# led_dip.net
KiCad netlist of a schematic drawn in EAGLE
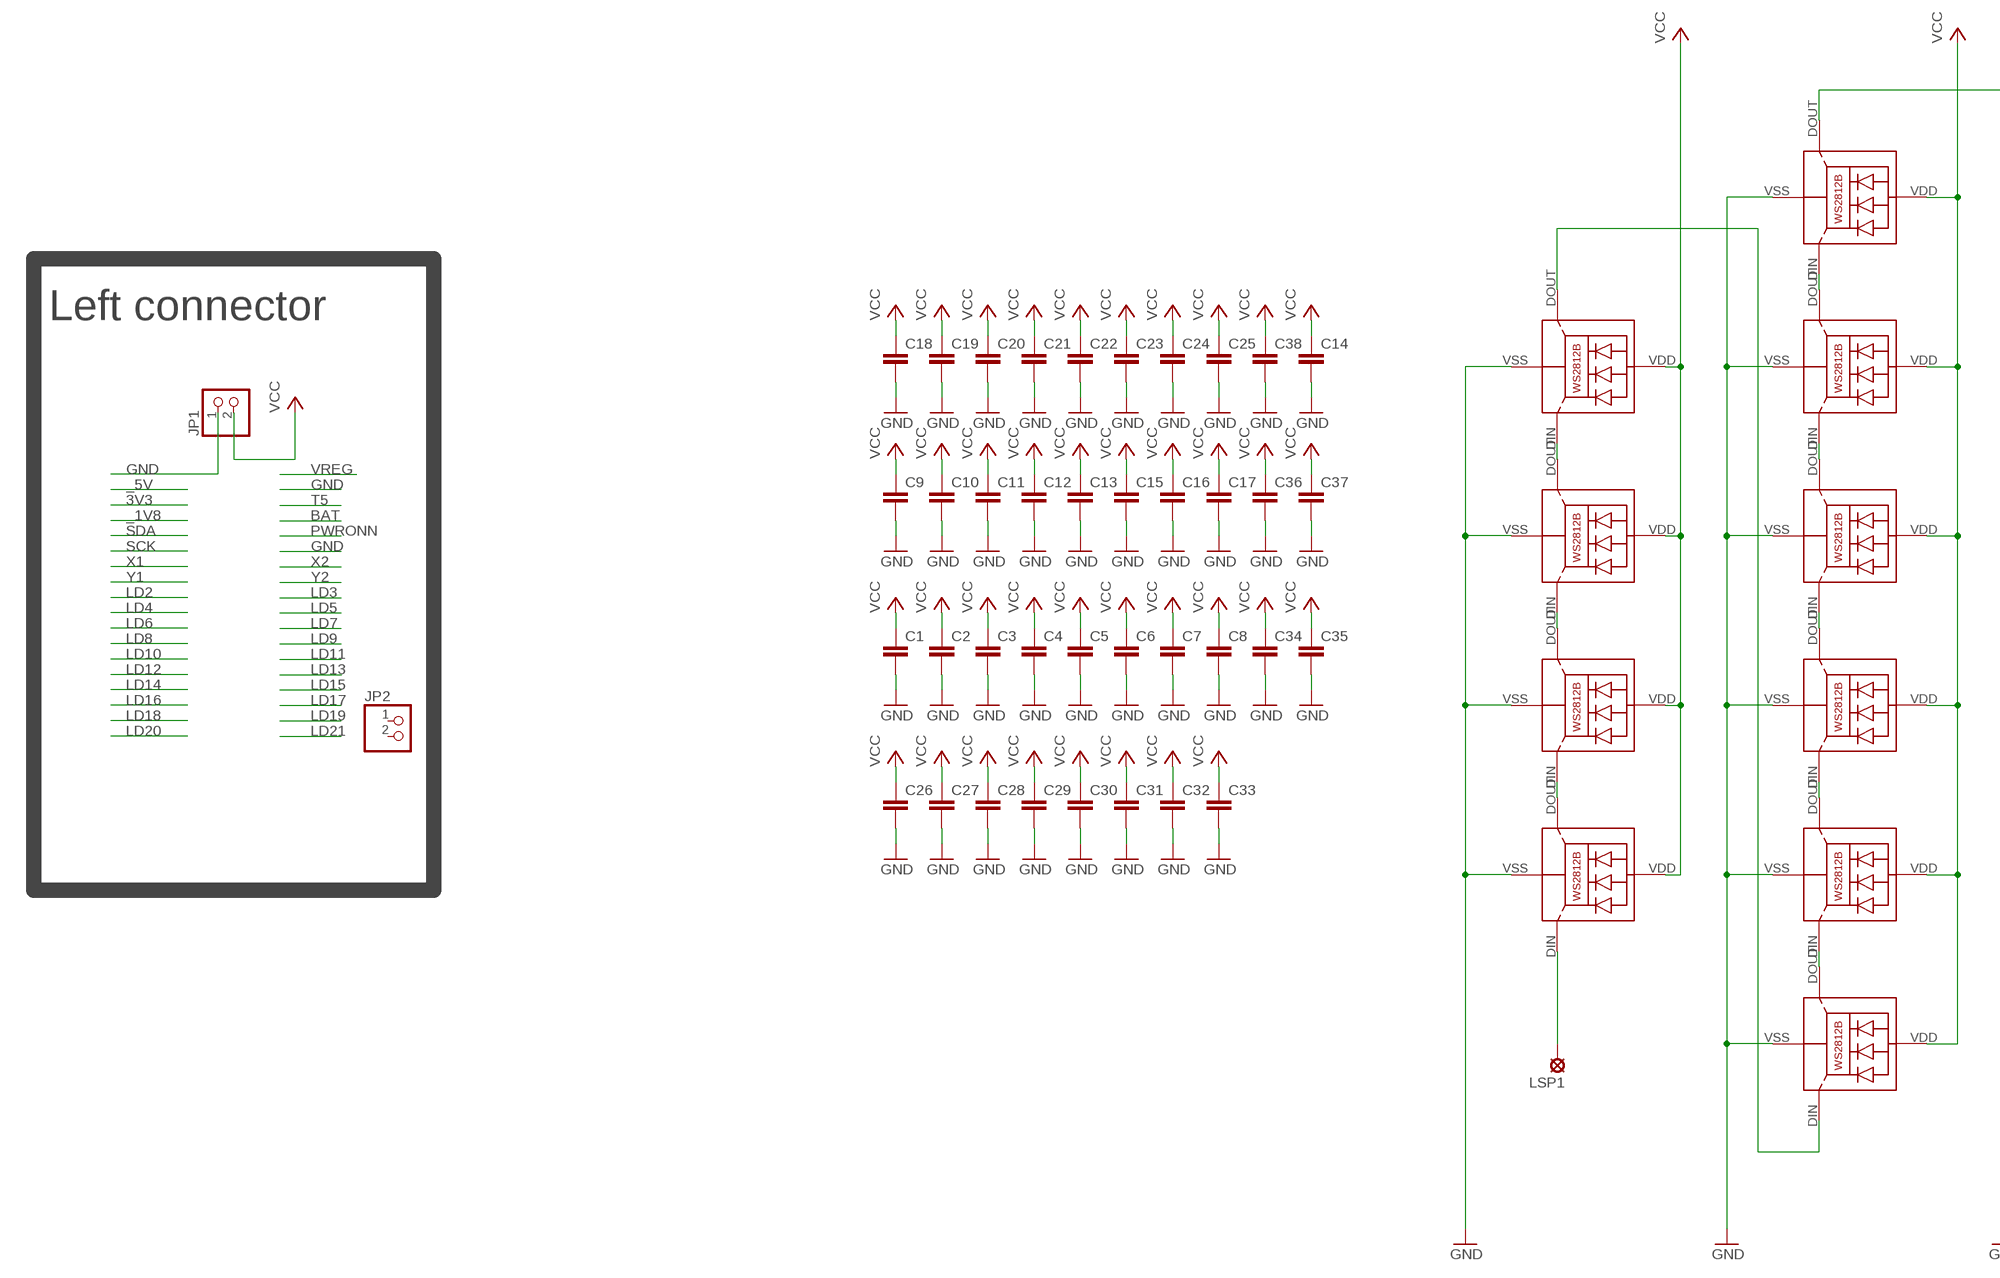
[diagram p0: schematic, sheet 1, part 1 of 2]
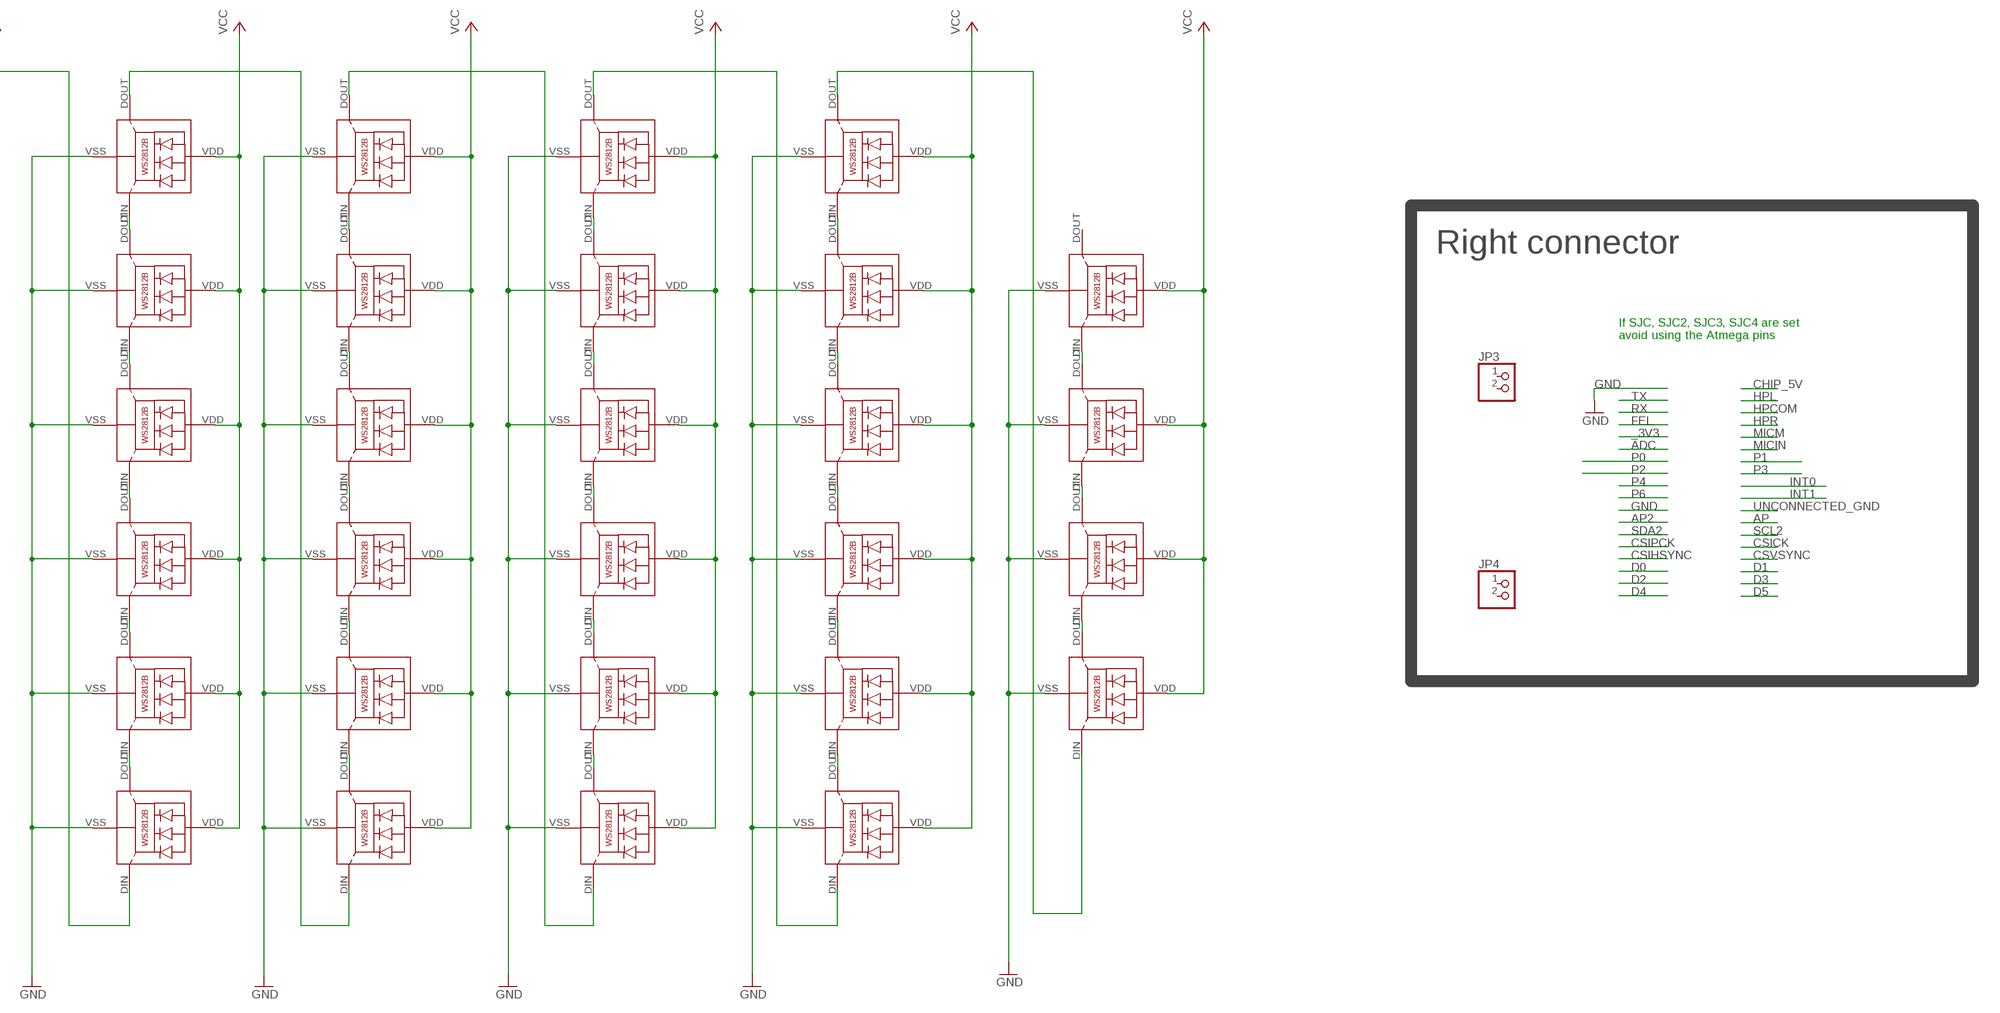
[diagram p1: schematic, sheet 1, part 2 of 2]

(export (version "E")
  (design (tool "Eeschema 10.0.6"))
  (components
    (comp (ref "C1")
      (value "C-EUC0805")
      (footprint "eagle-import:C0805")
      (libsource (lib "eagle-import") (part "C-EUC0805"))
    )
    (comp (ref "C2")
      (value "C-EUC0805")
      (footprint "eagle-import:C0805")
      (libsource (lib "eagle-import") (part "C-EUC0805"))
    )
    (comp (ref "C3")
      (value "C-EUC0805")
      (footprint "eagle-import:C0805")
      (libsource (lib "eagle-import") (part "C-EUC0805"))
    )
    (comp (ref "C4")
      (value "C-EUC0805")
      (footprint "eagle-import:C0805")
      (libsource (lib "eagle-import") (part "C-EUC0805"))
    )
    (comp (ref "C5")
      (value "C-EUC0805")
      (footprint "eagle-import:C0805")
      (libsource (lib "eagle-import") (part "C-EUC0805"))
    )
    (comp (ref "C6")
      (value "C-EUC0805")
      (footprint "eagle-import:C0805")
      (libsource (lib "eagle-import") (part "C-EUC0805"))
    )
    (comp (ref "C7")
      (value "C-EUC0805")
      (footprint "eagle-import:C0805")
      (libsource (lib "eagle-import") (part "C-EUC0805"))
    )
    (comp (ref "C8")
      (value "C-EUC0805")
      (footprint "eagle-import:C0805")
      (libsource (lib "eagle-import") (part "C-EUC0805"))
    )
    (comp (ref "C9")
      (value "C-EUC0805")
      (footprint "eagle-import:C0805")
      (libsource (lib "eagle-import") (part "C-EUC0805"))
    )
    (comp (ref "C10")
      (value "C-EUC0805")
      (footprint "eagle-import:C0805")
      (libsource (lib "eagle-import") (part "C-EUC0805"))
    )
    (comp (ref "C11")
      (value "C-EUC0805")
      (footprint "eagle-import:C0805")
      (libsource (lib "eagle-import") (part "C-EUC0805"))
    )
    (comp (ref "C12")
      (value "C-EUC0805")
      (footprint "eagle-import:C0805")
      (libsource (lib "eagle-import") (part "C-EUC0805"))
    )
    (comp (ref "C13")
      (value "C-EUC0805")
      (footprint "eagle-import:C0805")
      (libsource (lib "eagle-import") (part "C-EUC0805"))
    )
    (comp (ref "C14")
      (value "C-EUC0805")
      (footprint "eagle-import:C0805")
      (libsource (lib "eagle-import") (part "C-EUC0805"))
    )
    (comp (ref "C15")
      (value "C-EUC0805")
      (footprint "eagle-import:C0805")
      (libsource (lib "eagle-import") (part "C-EUC0805"))
    )
    (comp (ref "C16")
      (value "C-EUC0805")
      (footprint "eagle-import:C0805")
      (libsource (lib "eagle-import") (part "C-EUC0805"))
    )
    (comp (ref "C17")
      (value "C-EUC0805")
      (footprint "eagle-import:C0805")
      (libsource (lib "eagle-import") (part "C-EUC0805"))
    )
    (comp (ref "C18")
      (value "C-EUC0805")
      (footprint "eagle-import:C0805")
      (libsource (lib "eagle-import") (part "C-EUC0805"))
    )
    (comp (ref "C19")
      (value "C-EUC0805")
      (footprint "eagle-import:C0805")
      (libsource (lib "eagle-import") (part "C-EUC0805"))
    )
    (comp (ref "C20")
      (value "C-EUC0805")
      (footprint "eagle-import:C0805")
      (libsource (lib "eagle-import") (part "C-EUC0805"))
    )
    (comp (ref "C21")
      (value "C-EUC0805")
      (footprint "eagle-import:C0805")
      (libsource (lib "eagle-import") (part "C-EUC0805"))
    )
    (comp (ref "C22")
      (value "C-EUC0805")
      (footprint "eagle-import:C0805")
      (libsource (lib "eagle-import") (part "C-EUC0805"))
    )
    (comp (ref "C23")
      (value "C-EUC0805")
      (footprint "eagle-import:C0805")
      (libsource (lib "eagle-import") (part "C-EUC0805"))
    )
    (comp (ref "C24")
      (value "C-EUC0805")
      (footprint "eagle-import:C0805")
      (libsource (lib "eagle-import") (part "C-EUC0805"))
    )
    (comp (ref "C25")
      (value "C-EUC0805")
      (footprint "eagle-import:C0805")
      (libsource (lib "eagle-import") (part "C-EUC0805"))
    )
    (comp (ref "C26")
      (value "C-EUC0805")
      (footprint "eagle-import:C0805")
      (libsource (lib "eagle-import") (part "C-EUC0805"))
    )
    (comp (ref "C27")
      (value "C-EUC0805")
      (footprint "eagle-import:C0805")
      (libsource (lib "eagle-import") (part "C-EUC0805"))
    )
    (comp (ref "C28")
      (value "C-EUC0805")
      (footprint "eagle-import:C0805")
      (libsource (lib "eagle-import") (part "C-EUC0805"))
    )
    (comp (ref "C29")
      (value "C-EUC0805")
      (footprint "eagle-import:C0805")
      (libsource (lib "eagle-import") (part "C-EUC0805"))
    )
    (comp (ref "C30")
      (value "C-EUC0805")
      (footprint "eagle-import:C0805")
      (libsource (lib "eagle-import") (part "C-EUC0805"))
    )
    (comp (ref "C31")
      (value "C-EUC0805")
      (footprint "eagle-import:C0805")
      (libsource (lib "eagle-import") (part "C-EUC0805"))
    )
    (comp (ref "C32")
      (value "C-EUC0805")
      (footprint "eagle-import:C0805")
      (libsource (lib "eagle-import") (part "C-EUC0805"))
    )
    (comp (ref "C33")
      (value "C-EUC0805")
      (footprint "eagle-import:C0805")
      (libsource (lib "eagle-import") (part "C-EUC0805"))
    )
    (comp (ref "C34")
      (value "C-EUC0805")
      (footprint "eagle-import:C0805")
      (libsource (lib "eagle-import") (part "C-EUC0805"))
    )
    (comp (ref "C35")
      (value "C-EUC0805")
      (footprint "eagle-import:C0805")
      (libsource (lib "eagle-import") (part "C-EUC0805"))
    )
    (comp (ref "C36")
      (value "C-EUC0805")
      (footprint "eagle-import:C0805")
      (libsource (lib "eagle-import") (part "C-EUC0805"))
    )
    (comp (ref "C37")
      (value "C-EUC0805")
      (footprint "eagle-import:C0805")
      (libsource (lib "eagle-import") (part "C-EUC0805"))
    )
    (comp (ref "C38")
      (value "C-EUC0805")
      (footprint "eagle-import:C0805")
      (libsource (lib "eagle-import") (part "C-EUC0805"))
    )
    (comp (ref "JP1")
      (value "PINHD-1X2")
      (footprint "eagle-import:1X02")
      (libsource (lib "eagle-import") (part "PINHD-1X2"))
    )
    (comp (ref "JP2")
      (value "PINHD-1X2")
      (footprint "eagle-import:1X02")
      (libsource (lib "eagle-import") (part "PINHD-1X2"))
    )
    (comp (ref "JP3")
      (value "PINHD-1X2")
      (footprint "eagle-import:1X02")
      (libsource (lib "eagle-import") (part "PINHD-1X2"))
    )
    (comp (ref "JP4")
      (value "PINHD-1X2")
      (footprint "eagle-import:1X02")
      (libsource (lib "eagle-import") (part "PINHD-1X2"))
    )
    (comp (ref "LED1")
      (value "WS2812B")
      (footprint "eagle-import:WS2812B")
      (libsource (lib "eagle-import") (part "WS2812B"))
    )
    (comp (ref "LED2")
      (value "WS2812B")
      (footprint "eagle-import:WS2812B")
      (libsource (lib "eagle-import") (part "WS2812B"))
    )
    (comp (ref "LED3")
      (value "WS2812B")
      (footprint "eagle-import:WS2812B")
      (libsource (lib "eagle-import") (part "WS2812B"))
    )
    (comp (ref "LED4")
      (value "WS2812B")
      (footprint "eagle-import:WS2812B")
      (libsource (lib "eagle-import") (part "WS2812B"))
    )
    (comp (ref "LED5")
      (value "WS2812B")
      (footprint "eagle-import:WS2812B")
      (libsource (lib "eagle-import") (part "WS2812B"))
    )
    (comp (ref "LED6")
      (value "WS2812B")
      (footprint "eagle-import:WS2812B")
      (libsource (lib "eagle-import") (part "WS2812B"))
    )
    (comp (ref "LED7")
      (value "WS2812B")
      (footprint "eagle-import:WS2812B")
      (libsource (lib "eagle-import") (part "WS2812B"))
    )
    (comp (ref "LED8")
      (value "WS2812B")
      (footprint "eagle-import:WS2812B")
      (libsource (lib "eagle-import") (part "WS2812B"))
    )
    (comp (ref "LED9")
      (value "WS2812B")
      (footprint "eagle-import:WS2812B")
      (libsource (lib "eagle-import") (part "WS2812B"))
    )
    (comp (ref "LED10")
      (value "WS2812B")
      (footprint "eagle-import:WS2812B")
      (libsource (lib "eagle-import") (part "WS2812B"))
    )
    (comp (ref "LED11")
      (value "WS2812B")
      (footprint "eagle-import:WS2812B")
      (libsource (lib "eagle-import") (part "WS2812B"))
    )
    (comp (ref "LED12")
      (value "WS2812B")
      (footprint "eagle-import:WS2812B")
      (libsource (lib "eagle-import") (part "WS2812B"))
    )
    (comp (ref "LED13")
      (value "WS2812B")
      (footprint "eagle-import:WS2812B")
      (libsource (lib "eagle-import") (part "WS2812B"))
    )
    (comp (ref "LED14")
      (value "WS2812B")
      (footprint "eagle-import:WS2812B")
      (libsource (lib "eagle-import") (part "WS2812B"))
    )
    (comp (ref "LED15")
      (value "WS2812B")
      (footprint "eagle-import:WS2812B")
      (libsource (lib "eagle-import") (part "WS2812B"))
    )
    (comp (ref "LED16")
      (value "WS2812B")
      (footprint "eagle-import:WS2812B")
      (libsource (lib "eagle-import") (part "WS2812B"))
    )
    (comp (ref "LED17")
      (value "WS2812B")
      (footprint "eagle-import:WS2812B")
      (libsource (lib "eagle-import") (part "WS2812B"))
    )
    (comp (ref "LED18")
      (value "WS2812B")
      (footprint "eagle-import:WS2812B")
      (libsource (lib "eagle-import") (part "WS2812B"))
    )
    (comp (ref "LED19")
      (value "WS2812B")
      (footprint "eagle-import:WS2812B")
      (libsource (lib "eagle-import") (part "WS2812B"))
    )
    (comp (ref "LED20")
      (value "WS2812B")
      (footprint "eagle-import:WS2812B")
      (libsource (lib "eagle-import") (part "WS2812B"))
    )
    (comp (ref "LED21")
      (value "WS2812B")
      (footprint "eagle-import:WS2812B")
      (libsource (lib "eagle-import") (part "WS2812B"))
    )
    (comp (ref "LED22")
      (value "WS2812B")
      (footprint "eagle-import:WS2812B")
      (libsource (lib "eagle-import") (part "WS2812B"))
    )
    (comp (ref "LED23")
      (value "WS2812B")
      (footprint "eagle-import:WS2812B")
      (libsource (lib "eagle-import") (part "WS2812B"))
    )
    (comp (ref "LED24")
      (value "WS2812B")
      (footprint "eagle-import:WS2812B")
      (libsource (lib "eagle-import") (part "WS2812B"))
    )
    (comp (ref "LED25")
      (value "WS2812B")
      (footprint "eagle-import:WS2812B")
      (libsource (lib "eagle-import") (part "WS2812B"))
    )
    (comp (ref "LED26")
      (value "WS2812B")
      (footprint "eagle-import:WS2812B")
      (libsource (lib "eagle-import") (part "WS2812B"))
    )
    (comp (ref "LED27")
      (value "WS2812B")
      (footprint "eagle-import:WS2812B")
      (libsource (lib "eagle-import") (part "WS2812B"))
    )
    (comp (ref "LED28")
      (value "WS2812B")
      (footprint "eagle-import:WS2812B")
      (libsource (lib "eagle-import") (part "WS2812B"))
    )
    (comp (ref "LED30")
      (value "WS2812B")
      (footprint "eagle-import:WS2812B")
      (libsource (lib "eagle-import") (part "WS2812B"))
    )
    (comp (ref "LED31")
      (value "WS2812B")
      (footprint "eagle-import:WS2812B")
      (libsource (lib "eagle-import") (part "WS2812B"))
    )
    (comp (ref "LED32")
      (value "WS2812B")
      (footprint "eagle-import:WS2812B")
      (libsource (lib "eagle-import") (part "WS2812B"))
    )
    (comp (ref "LED33")
      (value "WS2812B")
      (footprint "eagle-import:WS2812B")
      (libsource (lib "eagle-import") (part "WS2812B"))
    )
    (comp (ref "LED34")
      (value "WS2812B")
      (footprint "eagle-import:WS2812B")
      (libsource (lib "eagle-import") (part "WS2812B"))
    )
    (comp (ref "LED35")
      (value "WS2812B")
      (footprint "eagle-import:WS2812B")
      (libsource (lib "eagle-import") (part "WS2812B"))
    )
    (comp (ref "LED36")
      (value "WS2812B")
      (footprint "eagle-import:WS2812B")
      (libsource (lib "eagle-import") (part "WS2812B"))
    )
    (comp (ref "LED37")
      (value "WS2812B")
      (footprint "eagle-import:WS2812B")
      (libsource (lib "eagle-import") (part "WS2812B"))
    )
    (comp (ref "LED38")
      (value "WS2812B")
      (footprint "eagle-import:WS2812B")
      (libsource (lib "eagle-import") (part "WS2812B"))
    )
    (comp (ref "LED39")
      (value "WS2812B")
      (footprint "eagle-import:WS2812B")
      (libsource (lib "eagle-import") (part "WS2812B"))
    )
    (comp (ref "LSP1")
      (value "LSP10")
      (footprint "eagle-import:LSP10")
      (libsource (lib "eagle-import") (part "LSP10"))
    )
  )
  (nets
    (net (code "68") (name "GND") (class "Default")
      (node (ref "C1") (pin "2") (pinfunction "2_2") (pintype "passive"))
      (node (ref "C10") (pin "2") (pinfunction "2_2") (pintype "passive"))
      (node (ref "C11") (pin "2") (pinfunction "2_2") (pintype "passive"))
      (node (ref "C12") (pin "2") (pinfunction "2_2") (pintype "passive"))
      (node (ref "C13") (pin "2") (pinfunction "2_2") (pintype "passive"))
      (node (ref "C14") (pin "2") (pinfunction "2_2") (pintype "passive"))
      (node (ref "C15") (pin "2") (pinfunction "2_2") (pintype "passive"))
      (node (ref "C16") (pin "2") (pinfunction "2_2") (pintype "passive"))
      (node (ref "C17") (pin "2") (pinfunction "2_2") (pintype "passive"))
      (node (ref "C18") (pin "2") (pinfunction "2_2") (pintype "passive"))
      (node (ref "C19") (pin "2") (pinfunction "2_2") (pintype "passive"))
      (node (ref "C2") (pin "2") (pinfunction "2_2") (pintype "passive"))
      (node (ref "C20") (pin "2") (pinfunction "2_2") (pintype "passive"))
      (node (ref "C21") (pin "2") (pinfunction "2_2") (pintype "passive"))
      (node (ref "C22") (pin "2") (pinfunction "2_2") (pintype "passive"))
      (node (ref "C23") (pin "2") (pinfunction "2_2") (pintype "passive"))
      (node (ref "C24") (pin "2") (pinfunction "2_2") (pintype "passive"))
      (node (ref "C25") (pin "2") (pinfunction "2_2") (pintype "passive"))
      (node (ref "C26") (pin "2") (pinfunction "2_2") (pintype "passive"))
      (node (ref "C27") (pin "2") (pinfunction "2_2") (pintype "passive"))
      (node (ref "C28") (pin "2") (pinfunction "2_2") (pintype "passive"))
      (node (ref "C29") (pin "2") (pinfunction "2_2") (pintype "passive"))
      (node (ref "C3") (pin "2") (pinfunction "2_2") (pintype "passive"))
      (node (ref "C30") (pin "2") (pinfunction "2_2") (pintype "passive"))
      (node (ref "C31") (pin "2") (pinfunction "2_2") (pintype "passive"))
      (node (ref "C32") (pin "2") (pinfunction "2_2") (pintype "passive"))
      (node (ref "C33") (pin "2") (pinfunction "2_2") (pintype "passive"))
      (node (ref "C34") (pin "2") (pinfunction "2_2") (pintype "passive"))
      (node (ref "C35") (pin "2") (pinfunction "2_2") (pintype "passive"))
      (node (ref "C36") (pin "2") (pinfunction "2_2") (pintype "passive"))
      (node (ref "C37") (pin "2") (pinfunction "2_2") (pintype "passive"))
      (node (ref "C38") (pin "2") (pinfunction "2_2") (pintype "passive"))
      (node (ref "C4") (pin "2") (pinfunction "2_2") (pintype "passive"))
      (node (ref "C5") (pin "2") (pinfunction "2_2") (pintype "passive"))
      (node (ref "C6") (pin "2") (pinfunction "2_2") (pintype "passive"))
      (node (ref "C7") (pin "2") (pinfunction "2_2") (pintype "passive"))
      (node (ref "C8") (pin "2") (pinfunction "2_2") (pintype "passive"))
      (node (ref "C9") (pin "2") (pinfunction "2_2") (pintype "passive"))
      (node (ref "JP1") (pin "1") (pinfunction "1_1") (pintype "passive"))
      (node (ref "LED1") (pin "VSS") (pinfunction "GND_VSS") (pintype "power_in"))
      (node (ref "LED10") (pin "VSS") (pinfunction "GND_VSS") (pintype "power_in"))
      (node (ref "LED11") (pin "VSS") (pinfunction "GND_VSS") (pintype "power_in"))
      (node (ref "LED12") (pin "VSS") (pinfunction "GND_VSS") (pintype "power_in"))
      (node (ref "LED13") (pin "VSS") (pinfunction "GND_VSS") (pintype "power_in"))
      (node (ref "LED14") (pin "VSS") (pinfunction "GND_VSS") (pintype "power_in"))
      (node (ref "LED15") (pin "VSS") (pinfunction "GND_VSS") (pintype "power_in"))
      (node (ref "LED16") (pin "VSS") (pinfunction "GND_VSS") (pintype "power_in"))
      (node (ref "LED17") (pin "VSS") (pinfunction "GND_VSS") (pintype "power_in"))
      (node (ref "LED18") (pin "VSS") (pinfunction "GND_VSS") (pintype "power_in"))
      (node (ref "LED19") (pin "VSS") (pinfunction "GND_VSS") (pintype "power_in"))
      (node (ref "LED2") (pin "VSS") (pinfunction "GND_VSS") (pintype "power_in"))
      (node (ref "LED20") (pin "VSS") (pinfunction "GND_VSS") (pintype "power_in"))
      (node (ref "LED21") (pin "VSS") (pinfunction "GND_VSS") (pintype "power_in"))
      (node (ref "LED22") (pin "VSS") (pinfunction "GND_VSS") (pintype "power_in"))
      (node (ref "LED23") (pin "VSS") (pinfunction "GND_VSS") (pintype "power_in"))
      (node (ref "LED24") (pin "VSS") (pinfunction "GND_VSS") (pintype "power_in"))
      (node (ref "LED25") (pin "VSS") (pinfunction "GND_VSS") (pintype "power_in"))
      (node (ref "LED26") (pin "VSS") (pinfunction "GND_VSS") (pintype "power_in"))
      (node (ref "LED27") (pin "VSS") (pinfunction "GND_VSS") (pintype "power_in"))
      (node (ref "LED28") (pin "VSS") (pinfunction "GND_VSS") (pintype "power_in"))
      (node (ref "LED3") (pin "VSS") (pinfunction "GND_VSS") (pintype "power_in"))
      (node (ref "LED30") (pin "VSS") (pinfunction "GND_VSS") (pintype "power_in"))
      (node (ref "LED31") (pin "VSS") (pinfunction "GND_VSS") (pintype "power_in"))
      (node (ref "LED32") (pin "VSS") (pinfunction "GND_VSS") (pintype "power_in"))
      (node (ref "LED33") (pin "VSS") (pinfunction "GND_VSS") (pintype "power_in"))
      (node (ref "LED34") (pin "VSS") (pinfunction "GND_VSS") (pintype "power_in"))
      (node (ref "LED35") (pin "VSS") (pinfunction "GND_VSS") (pintype "power_in"))
      (node (ref "LED36") (pin "VSS") (pinfunction "GND_VSS") (pintype "power_in"))
      (node (ref "LED37") (pin "VSS") (pinfunction "GND_VSS") (pintype "power_in"))
      (node (ref "LED38") (pin "VSS") (pinfunction "GND_VSS") (pintype "power_in"))
      (node (ref "LED39") (pin "VSS") (pinfunction "GND_VSS") (pintype "power_in"))
      (node (ref "LED4") (pin "VSS") (pinfunction "GND_VSS") (pintype "power_in"))
      (node (ref "LED5") (pin "VSS") (pinfunction "GND_VSS") (pintype "power_in"))
      (node (ref "LED6") (pin "VSS") (pinfunction "GND_VSS") (pintype "power_in"))
      (node (ref "LED7") (pin "VSS") (pinfunction "GND_VSS") (pintype "power_in"))
      (node (ref "LED8") (pin "VSS") (pinfunction "GND_VSS") (pintype "power_in"))
      (node (ref "LED9") (pin "VSS") (pinfunction "GND_VSS") (pintype "power_in"))
    )
    (net (code "69") (name "Net-(LED1-DI)") (class "Default")
      (node (ref "LED1") (pin "DIN") (pinfunction "DI_DIN") (pintype "input"))
      (node (ref "LED3") (pin "DOUT") (pinfunction "DO_DOUT") (pintype "output"))
    )
    (net (code "70") (name "Net-(LED1-DO)") (class "Default")
      (node (ref "LED1") (pin "DOUT") (pinfunction "DO_DOUT") (pintype "output"))
      (node (ref "LED2") (pin "DIN") (pinfunction "DI_DIN") (pintype "input"))
    )
    (net (code "71") (name "Net-(LED2-DO)") (class "Default")
      (node (ref "LED2") (pin "DOUT") (pinfunction "DO_DOUT") (pintype "output"))
      (node (ref "LED28") (pin "DIN") (pinfunction "DI_DIN") (pintype "input"))
    )
    (net (code "72") (name "Net-(LED6-DI)") (class "Default")
      (node (ref "LED6") (pin "DIN") (pinfunction "DI_DIN") (pintype "input"))
      (node (ref "LED9") (pin "DOUT") (pinfunction "DO_DOUT") (pintype "output"))
    )
    (net (code "73") (name "Net-(LED6-DO)") (class "Default")
      (node (ref "LED6") (pin "DOUT") (pinfunction "DO_DOUT") (pintype "output"))
      (node (ref "LED7") (pin "DIN") (pinfunction "DI_DIN") (pintype "input"))
    )
    (net (code "74") (name "Net-(LED7-DO)") (class "Default")
      (node (ref "LED7") (pin "DOUT") (pinfunction "DO_DOUT") (pintype "output"))
      (node (ref "LED8") (pin "DIN") (pinfunction "DI_DIN") (pintype "input"))
    )
    (net (code "75") (name "Net-(LED10-DI)") (class "Default")
      (node (ref "LED10") (pin "DIN") (pinfunction "DI_DIN") (pintype "input"))
      (node (ref "LED25") (pin "DOUT") (pinfunction "DO_DOUT") (pintype "output"))
    )
    (net (code "76") (name "Net-(LED10-DO)") (class "Default")
      (node (ref "LED10") (pin "DOUT") (pinfunction "DO_DOUT") (pintype "output"))
      (node (ref "LED19") (pin "DIN") (pinfunction "DI_DIN") (pintype "input"))
    )
    (net (code "77") (name "Net-(LED11-DI)") (class "Default")
      (node (ref "LED11") (pin "DIN") (pinfunction "DI_DIN") (pintype "input"))
      (node (ref "LED13") (pin "DOUT") (pinfunction "DO_DOUT") (pintype "output"))
    )
    (net (code "78") (name "Net-(LED11-DO)") (class "Default")
      (node (ref "LED11") (pin "DOUT") (pinfunction "DO_DOUT") (pintype "output"))
      (node (ref "LED25") (pin "DIN") (pinfunction "DI_DIN") (pintype "input"))
    )
    (net (code "79") (name "Net-(LED12-DI)") (class "Default")
      (node (ref "LED12") (pin "DIN") (pinfunction "DI_DIN") (pintype "input"))
      (node (ref "LED20") (pin "DOUT") (pinfunction "DO_DOUT") (pintype "output"))
    )
    (net (code "80") (name "Net-(LED12-DO)") (class "Default")
      (node (ref "LED12") (pin "DOUT") (pinfunction "DO_DOUT") (pintype "output"))
      (node (ref "LED9") (pin "DIN") (pinfunction "DI_DIN") (pintype "input"))
    )
    (net (code "81") (name "Net-(LED13-DI)") (class "Default")
      (node (ref "LED13") (pin "DIN") (pinfunction "DI_DIN") (pintype "input"))
      (node (ref "LED15") (pin "DOUT") (pinfunction "DO_DOUT") (pintype "output"))
    )
    (net (code "82") (name "Net-(LED14-DI)") (class "Default")
      (node (ref "LED14") (pin "DIN") (pinfunction "DI_DIN") (pintype "input"))
      (node (ref "LSP1") (pin "MP") (pinfunction "MP_MP") (pintype "passive"))
    )
    (net (code "83") (name "Net-(LED14-DO)") (class "Default")
      (node (ref "LED14") (pin "DOUT") (pinfunction "DO_DOUT") (pintype "output"))
      (node (ref "LED16") (pin "DIN") (pinfunction "DI_DIN") (pintype "input"))
    )
    (net (code "84") (name "Net-(LED15-DI)") (class "Default")
      (node (ref "LED15") (pin "DIN") (pinfunction "DI_DIN") (pintype "input"))
      (node (ref "LED33") (pin "DOUT") (pinfunction "DO_DOUT") (pintype "output"))
    )
    (net (code "85") (name "Net-(LED16-DO)") (class "Default")
      (node (ref "LED16") (pin "DOUT") (pinfunction "DO_DOUT") (pintype "output"))
      (node (ref "LED20") (pin "DIN") (pinfunction "DI_DIN") (pintype "input"))
    )
    (net (code "86") (name "Net-(LED17-DI)") (class "Default")
      (node (ref "LED17") (pin "DIN") (pinfunction "DI_DIN") (pintype "input"))
      (node (ref "LED22") (pin "DOUT") (pinfunction "DO_DOUT") (pintype "output"))
    )
    (net (code "87") (name "Net-(LED17-DO)") (class "Default")
      (node (ref "LED17") (pin "DOUT") (pinfunction "DO_DOUT") (pintype "output"))
      (node (ref "LED27") (pin "DIN") (pinfunction "DI_DIN") (pintype "input"))
    )
    (net (code "88") (name "Net-(LED18-DI)") (class "Default")
      (node (ref "LED18") (pin "DIN") (pinfunction "DI_DIN") (pintype "input"))
      (node (ref "LED8") (pin "DOUT") (pinfunction "DO_DOUT") (pintype "output"))
    )
    (net (code "89") (name "Net-(LED18-DO)") (class "Default")
      (node (ref "LED18") (pin "DOUT") (pinfunction "DO_DOUT") (pintype "output"))
      (node (ref "LED3") (pin "DIN") (pinfunction "DI_DIN") (pintype "input"))
    )
    (net (code "90") (name "Net-(LED19-DO)") (class "Default")
      (node (ref "LED19") (pin "DOUT") (pinfunction "DO_DOUT") (pintype "output"))
      (node (ref "LED26") (pin "DIN") (pinfunction "DI_DIN") (pintype "input"))
    )
    (net (code "91") (name "Net-(LED21-DI)") (class "Default")
      (node (ref "LED21") (pin "DIN") (pinfunction "DI_DIN") (pintype "input"))
      (node (ref "LED26") (pin "DOUT") (pinfunction "DO_DOUT") (pintype "output"))
    )
    (net (code "92") (name "Net-(LED21-DO)") (class "Default")
      (node (ref "LED21") (pin "DOUT") (pinfunction "DO_DOUT") (pintype "output"))
      (node (ref "LED23") (pin "DIN") (pinfunction "DI_DIN") (pintype "input"))
    )
    (net (code "93") (name "Net-(LED22-DI)") (class "Default")
      (node (ref "LED22") (pin "DIN") (pinfunction "DI_DIN") (pintype "input"))
      (node (ref "LED28") (pin "DOUT") (pinfunction "DO_DOUT") (pintype "output"))
    )
    (net (code "94") (name "Net-(LED23-DO)") (class "Default")
      (node (ref "LED23") (pin "DOUT") (pinfunction "DO_DOUT") (pintype "output"))
      (node (ref "LED24") (pin "DIN") (pinfunction "DI_DIN") (pintype "input"))
    )
    (net (code "95") (name "Net-(LED27-DO)") (class "Default")
      (node (ref "LED27") (pin "DOUT") (pinfunction "DO_DOUT") (pintype "output"))
      (node (ref "LED37") (pin "DIN") (pinfunction "DI_DIN") (pintype "input"))
    )
    (net (code "96") (name "Net-(LED30-DI)") (class "Default")
      (node (ref "LED30") (pin "DIN") (pinfunction "DI_DIN") (pintype "input"))
      (node (ref "LED31") (pin "DOUT") (pinfunction "DO_DOUT") (pintype "output"))
    )
    (net (code "97") (name "Net-(LED30-DO)") (class "Default")
      (node (ref "LED30") (pin "DOUT") (pinfunction "DO_DOUT") (pintype "output"))
      (node (ref "LED38") (pin "DIN") (pinfunction "DI_DIN") (pintype "input"))
    )
    (net (code "98") (name "Net-(LED31-DI)") (class "Default")
      (node (ref "LED31") (pin "DIN") (pinfunction "DI_DIN") (pintype "input"))
      (node (ref "LED4") (pin "DOUT") (pinfunction "DO_DOUT") (pintype "output"))
    )
    (net (code "99") (name "Net-(LED32-DI)") (class "Default")
      (node (ref "LED32") (pin "DIN") (pinfunction "DI_DIN") (pintype "input"))
      (node (ref "LED5") (pin "DOUT") (pinfunction "DO_DOUT") (pintype "output"))
    )
    (net (code "100") (name "Net-(LED32-DO)") (class "Default")
      (node (ref "LED32") (pin "DOUT") (pinfunction "DO_DOUT") (pintype "output"))
      (node (ref "LED33") (pin "DIN") (pinfunction "DI_DIN") (pintype "input"))
    )
    (net (code "101") (name "Net-(LED34-DI)") (class "Default")
      (node (ref "LED34") (pin "DIN") (pinfunction "DI_DIN") (pintype "input"))
      (node (ref "LED36") (pin "DOUT") (pinfunction "DO_DOUT") (pintype "output"))
    )
    (net (code "102") (name "Net-(LED34-DO)") (class "Default")
      (node (ref "LED34") (pin "DOUT") (pinfunction "DO_DOUT") (pintype "output"))
      (node (ref "LED4") (pin "DIN") (pinfunction "DI_DIN") (pintype "input"))
    )
    (net (code "103") (name "Net-(LED35-DI)") (class "Default")
      (node (ref "LED35") (pin "DIN") (pinfunction "DI_DIN") (pintype "input"))
      (node (ref "LED39") (pin "DOUT") (pinfunction "DO_DOUT") (pintype "output"))
    )
    (net (code "104") (name "Net-(LED35-DO)") (class "Default")
      (node (ref "LED35") (pin "DOUT") (pinfunction "DO_DOUT") (pintype "output"))
      (node (ref "LED5") (pin "DIN") (pinfunction "DI_DIN") (pintype "input"))
    )
    (net (code "105") (name "Net-(LED36-DI)") (class "Default")
      (node (ref "LED36") (pin "DIN") (pinfunction "DI_DIN") (pintype "input"))
      (node (ref "LED37") (pin "DOUT") (pinfunction "DO_DOUT") (pintype "output"))
    )
    (net (code "106") (name "Net-(LED38-DO)") (class "Default")
      (node (ref "LED38") (pin "DOUT") (pinfunction "DO_DOUT") (pintype "output"))
      (node (ref "LED39") (pin "DIN") (pinfunction "DI_DIN") (pintype "input"))
    )
    (net (code "107") (name "VCC") (class "Default")
      (node (ref "C1") (pin "1") (pinfunction "1_1") (pintype "passive"))
      (node (ref "C10") (pin "1") (pinfunction "1_1") (pintype "passive"))
      (node (ref "C11") (pin "1") (pinfunction "1_1") (pintype "passive"))
      (node (ref "C12") (pin "1") (pinfunction "1_1") (pintype "passive"))
      (node (ref "C13") (pin "1") (pinfunction "1_1") (pintype "passive"))
      (node (ref "C14") (pin "1") (pinfunction "1_1") (pintype "passive"))
      (node (ref "C15") (pin "1") (pinfunction "1_1") (pintype "passive"))
      (node (ref "C16") (pin "1") (pinfunction "1_1") (pintype "passive"))
      (node (ref "C17") (pin "1") (pinfunction "1_1") (pintype "passive"))
      (node (ref "C18") (pin "1") (pinfunction "1_1") (pintype "passive"))
      (node (ref "C19") (pin "1") (pinfunction "1_1") (pintype "passive"))
      (node (ref "C2") (pin "1") (pinfunction "1_1") (pintype "passive"))
      (node (ref "C20") (pin "1") (pinfunction "1_1") (pintype "passive"))
      (node (ref "C21") (pin "1") (pinfunction "1_1") (pintype "passive"))
      (node (ref "C22") (pin "1") (pinfunction "1_1") (pintype "passive"))
      (node (ref "C23") (pin "1") (pinfunction "1_1") (pintype "passive"))
      (node (ref "C24") (pin "1") (pinfunction "1_1") (pintype "passive"))
      (node (ref "C25") (pin "1") (pinfunction "1_1") (pintype "passive"))
      (node (ref "C26") (pin "1") (pinfunction "1_1") (pintype "passive"))
      (node (ref "C27") (pin "1") (pinfunction "1_1") (pintype "passive"))
      (node (ref "C28") (pin "1") (pinfunction "1_1") (pintype "passive"))
      (node (ref "C29") (pin "1") (pinfunction "1_1") (pintype "passive"))
      (node (ref "C3") (pin "1") (pinfunction "1_1") (pintype "passive"))
      (node (ref "C30") (pin "1") (pinfunction "1_1") (pintype "passive"))
      (node (ref "C31") (pin "1") (pinfunction "1_1") (pintype "passive"))
      (node (ref "C32") (pin "1") (pinfunction "1_1") (pintype "passive"))
      (node (ref "C33") (pin "1") (pinfunction "1_1") (pintype "passive"))
      (node (ref "C34") (pin "1") (pinfunction "1_1") (pintype "passive"))
      (node (ref "C35") (pin "1") (pinfunction "1_1") (pintype "passive"))
      (node (ref "C36") (pin "1") (pinfunction "1_1") (pintype "passive"))
      (node (ref "C37") (pin "1") (pinfunction "1_1") (pintype "passive"))
      (node (ref "C38") (pin "1") (pinfunction "1_1") (pintype "passive"))
      (node (ref "C4") (pin "1") (pinfunction "1_1") (pintype "passive"))
      (node (ref "C5") (pin "1") (pinfunction "1_1") (pintype "passive"))
      (node (ref "C6") (pin "1") (pinfunction "1_1") (pintype "passive"))
      (node (ref "C7") (pin "1") (pinfunction "1_1") (pintype "passive"))
      (node (ref "C8") (pin "1") (pinfunction "1_1") (pintype "passive"))
      (node (ref "C9") (pin "1") (pinfunction "1_1") (pintype "passive"))
      (node (ref "JP1") (pin "2") (pinfunction "2_2") (pintype "passive"))
      (node (ref "LED1") (pin "VDD") (pinfunction "VDD_VDD") (pintype "power_in"))
      (node (ref "LED10") (pin "VDD") (pinfunction "VDD_VDD") (pintype "power_in"))
      (node (ref "LED11") (pin "VDD") (pinfunction "VDD_VDD") (pintype "power_in"))
      (node (ref "LED12") (pin "VDD") (pinfunction "VDD_VDD") (pintype "power_in"))
      (node (ref "LED13") (pin "VDD") (pinfunction "VDD_VDD") (pintype "power_in"))
      (node (ref "LED14") (pin "VDD") (pinfunction "VDD_VDD") (pintype "power_in"))
      (node (ref "LED15") (pin "VDD") (pinfunction "VDD_VDD") (pintype "power_in"))
      (node (ref "LED16") (pin "VDD") (pinfunction "VDD_VDD") (pintype "power_in"))
      (node (ref "LED17") (pin "VDD") (pinfunction "VDD_VDD") (pintype "power_in"))
      (node (ref "LED18") (pin "VDD") (pinfunction "VDD_VDD") (pintype "power_in"))
      (node (ref "LED19") (pin "VDD") (pinfunction "VDD_VDD") (pintype "power_in"))
      (node (ref "LED2") (pin "VDD") (pinfunction "VDD_VDD") (pintype "power_in"))
      (node (ref "LED20") (pin "VDD") (pinfunction "VDD_VDD") (pintype "power_in"))
      (node (ref "LED21") (pin "VDD") (pinfunction "VDD_VDD") (pintype "power_in"))
      (node (ref "LED22") (pin "VDD") (pinfunction "VDD_VDD") (pintype "power_in"))
      (node (ref "LED23") (pin "VDD") (pinfunction "VDD_VDD") (pintype "power_in"))
      (node (ref "LED24") (pin "VDD") (pinfunction "VDD_VDD") (pintype "power_in"))
      (node (ref "LED25") (pin "VDD") (pinfunction "VDD_VDD") (pintype "power_in"))
      (node (ref "LED26") (pin "VDD") (pinfunction "VDD_VDD") (pintype "power_in"))
      (node (ref "LED27") (pin "VDD") (pinfunction "VDD_VDD") (pintype "power_in"))
      (node (ref "LED28") (pin "VDD") (pinfunction "VDD_VDD") (pintype "power_in"))
      (node (ref "LED3") (pin "VDD") (pinfunction "VDD_VDD") (pintype "power_in"))
      (node (ref "LED30") (pin "VDD") (pinfunction "VDD_VDD") (pintype "power_in"))
      (node (ref "LED31") (pin "VDD") (pinfunction "VDD_VDD") (pintype "power_in"))
      (node (ref "LED32") (pin "VDD") (pinfunction "VDD_VDD") (pintype "power_in"))
      (node (ref "LED33") (pin "VDD") (pinfunction "VDD_VDD") (pintype "power_in"))
      (node (ref "LED34") (pin "VDD") (pinfunction "VDD_VDD") (pintype "power_in"))
      (node (ref "LED35") (pin "VDD") (pinfunction "VDD_VDD") (pintype "power_in"))
      (node (ref "LED36") (pin "VDD") (pinfunction "VDD_VDD") (pintype "power_in"))
      (node (ref "LED37") (pin "VDD") (pinfunction "VDD_VDD") (pintype "power_in"))
      (node (ref "LED38") (pin "VDD") (pinfunction "VDD_VDD") (pintype "power_in"))
      (node (ref "LED39") (pin "VDD") (pinfunction "VDD_VDD") (pintype "power_in"))
      (node (ref "LED4") (pin "VDD") (pinfunction "VDD_VDD") (pintype "power_in"))
      (node (ref "LED5") (pin "VDD") (pinfunction "VDD_VDD") (pintype "power_in"))
      (node (ref "LED6") (pin "VDD") (pinfunction "VDD_VDD") (pintype "power_in"))
      (node (ref "LED7") (pin "VDD") (pinfunction "VDD_VDD") (pintype "power_in"))
      (node (ref "LED8") (pin "VDD") (pinfunction "VDD_VDD") (pintype "power_in"))
      (node (ref "LED9") (pin "VDD") (pinfunction "VDD_VDD") (pintype "power_in"))
    )
    (net (code "108") (name "unconnected-(JP2-Pad1)") (class "Default")
      (node (ref "JP2") (pin "1") (pinfunction "1_1") (pintype "passive"))
    )
    (net (code "109") (name "unconnected-(JP2-Pad2)") (class "Default")
      (node (ref "JP2") (pin "2") (pinfunction "2_2") (pintype "passive"))
    )
    (net (code "110") (name "unconnected-(JP3-Pad1)") (class "Default")
      (node (ref "JP3") (pin "1") (pinfunction "1_1") (pintype "passive"))
    )
    (net (code "111") (name "unconnected-(JP3-Pad2)") (class "Default")
      (node (ref "JP3") (pin "2") (pinfunction "2_2") (pintype "passive"))
    )
    (net (code "112") (name "unconnected-(JP4-Pad1)") (class "Default")
      (node (ref "JP4") (pin "1") (pinfunction "1_1") (pintype "passive"))
    )
    (net (code "113") (name "unconnected-(JP4-Pad2)") (class "Default")
      (node (ref "JP4") (pin "2") (pinfunction "2_2") (pintype "passive"))
    )
    (net (code "114") (name "unconnected-(LED24-DO-PadDOUT)") (class "Default")
      (node (ref "LED24") (pin "DOUT") (pinfunction "DO_DOUT") (pintype "output"))
    )
  )
)
